# Autonomous-Car_Schematic-Extended.net
KiCad netlist of a schematic drawn in EAGLE
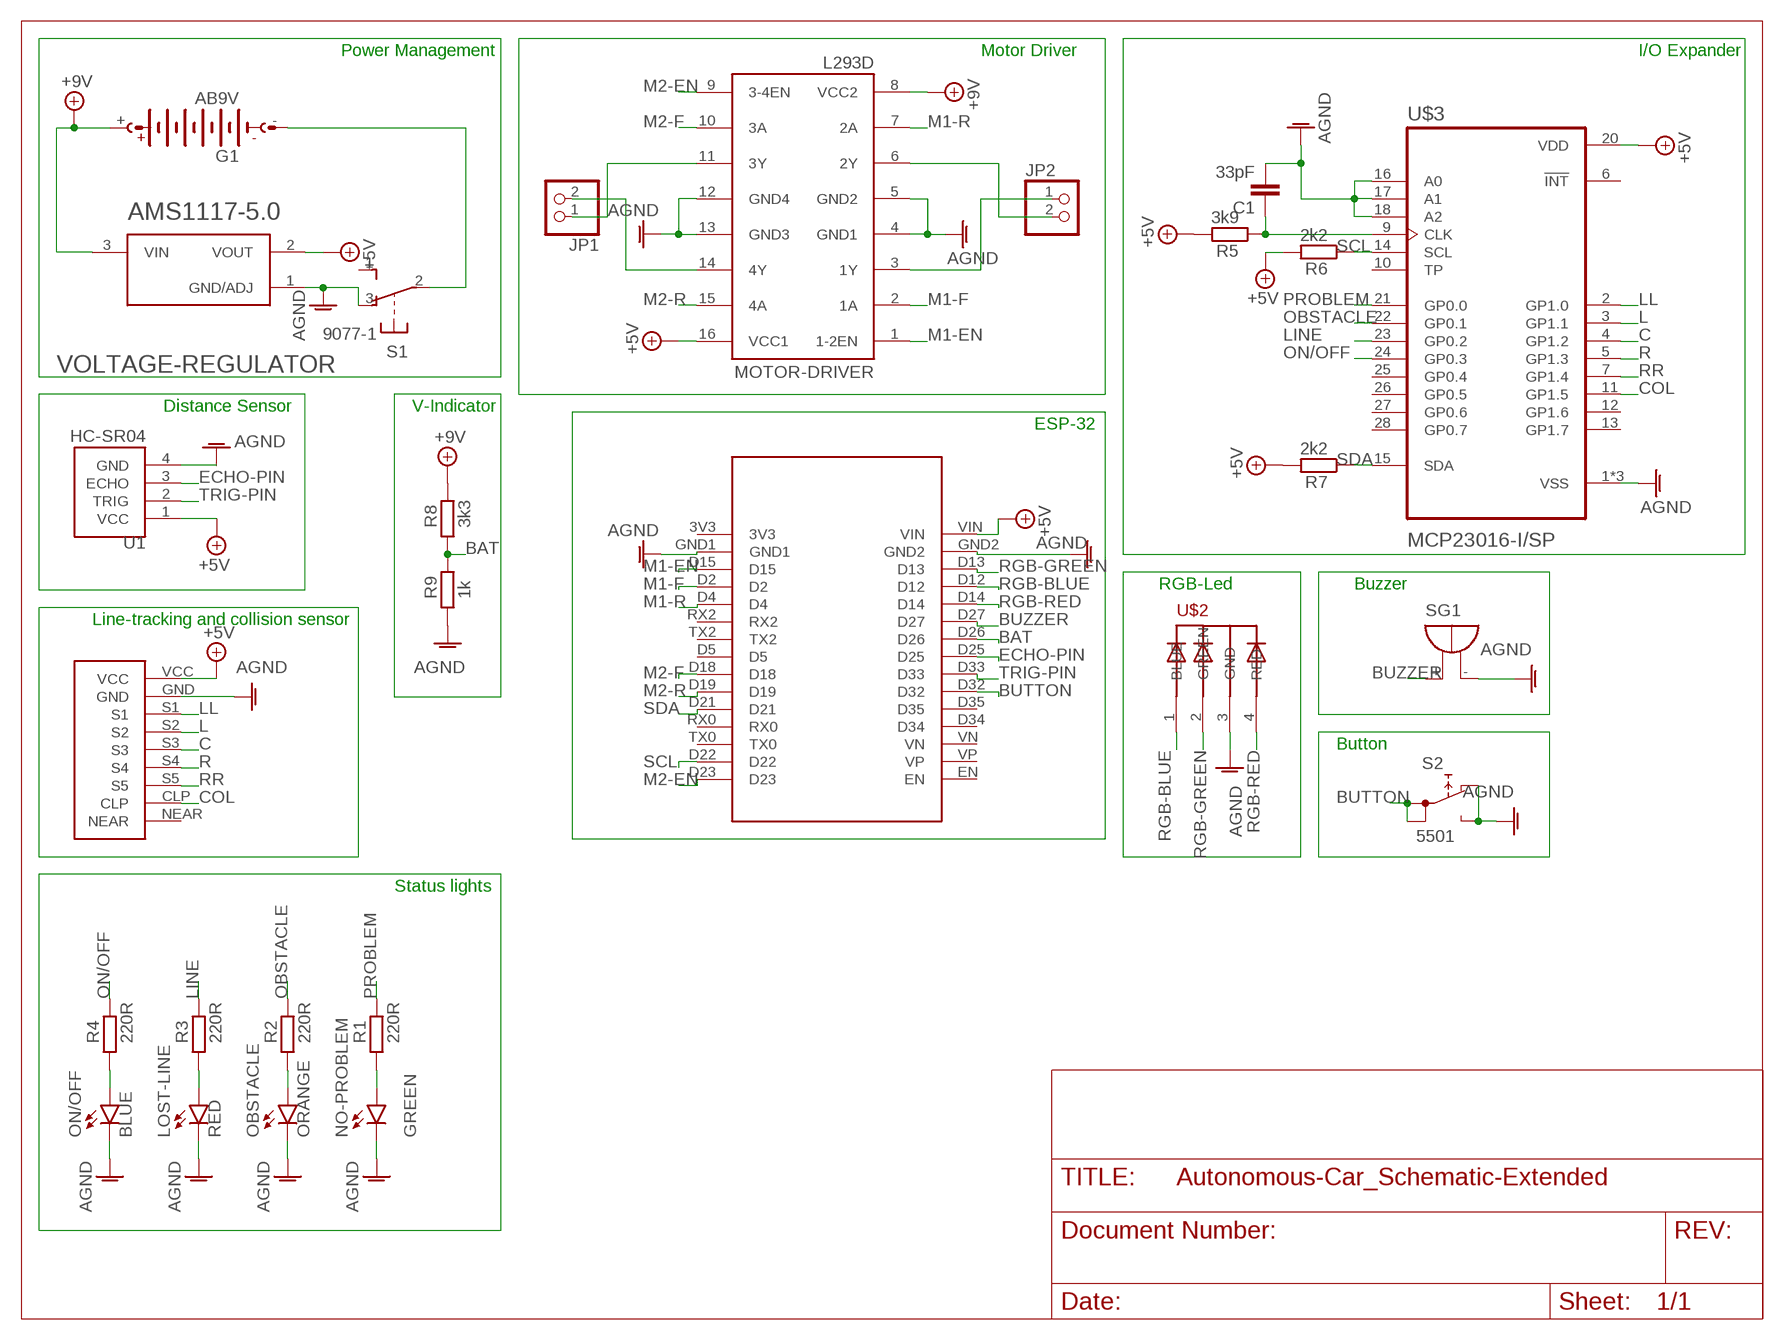
[diagram p0: schematic, sheet 1]

(export (version "E")
  (design (tool "Eeschema 10.0.6"))
  (components
    (comp (ref "C1")
      (value "33pF")
      (footprint "eagle-import:C025-024X044")
      (libsource (lib "eagle-import") (part "C-EU025-024X044"))
    )
    (comp (ref "G1")
      (value "AB9V")
      (footprint "eagle-import:AB9V")
      (libsource (lib "eagle-import") (part "AB9V"))
    )
    (comp (ref "JP1")
      (value "PINHD-1X2")
      (footprint "eagle-import:1X02")
      (libsource (lib "eagle-import") (part "PINHD-1X2"))
    )
    (comp (ref "JP2")
      (value "PINHD-1X2")
      (footprint "eagle-import:1X02")
      (libsource (lib "eagle-import") (part "PINHD-1X2"))
    )
    (comp (ref "LINETRACKER")
      (value "5XTCRT5000")
      (footprint "eagle-import:5XTCRT5000")
      (libsource (lib "eagle-import") (part "5XTCRT5000"))
    )
    (comp (ref "LOST-LINE")
      (value "RED")
      (footprint "eagle-import:LED5MM")
      (libsource (lib "eagle-import") (part "LED5MM"))
    )
    (comp (ref "MOTOR-DRIVER")
      (value "L293D")
      (footprint "eagle-import:DIL16")
      (libsource (lib "eagle-import") (part "L293D"))
    )
    (comp (ref "NO-PROBLEM")
      (value "GREEN")
      (footprint "eagle-import:LED5MM")
      (libsource (lib "eagle-import") (part "LED5MM"))
    )
    (comp (ref "OBSTACLE")
      (value "ORANGE")
      (footprint "eagle-import:LED5MM")
      (libsource (lib "eagle-import") (part "LED5MM"))
    )
    (comp (ref "ON/OFF")
      (value "BLUE")
      (footprint "eagle-import:LED5MM")
      (libsource (lib "eagle-import") (part "LED5MM"))
    )
    (comp (ref "R1")
      (value "220R")
      (footprint "eagle-import:0204_5")
      (libsource (lib "eagle-import") (part "R-EU_0204/5"))
    )
    (comp (ref "R2")
      (value "220R")
      (footprint "eagle-import:0204_5")
      (libsource (lib "eagle-import") (part "R-EU_0204/5"))
    )
    (comp (ref "R3")
      (value "220R")
      (footprint "eagle-import:0204_5")
      (libsource (lib "eagle-import") (part "R-EU_0204/5"))
    )
    (comp (ref "R4")
      (value "220R")
      (footprint "eagle-import:0204_5")
      (libsource (lib "eagle-import") (part "R-EU_0204/5"))
    )
    (comp (ref "R5")
      (value "3k9")
      (footprint "eagle-import:0204_5")
      (libsource (lib "eagle-import") (part "R-EU_0204/5"))
    )
    (comp (ref "R6")
      (value "2k2")
      (footprint "eagle-import:0204_5")
      (libsource (lib "eagle-import") (part "R-EU_0204/5"))
    )
    (comp (ref "R7")
      (value "2k2")
      (footprint "eagle-import:0204_5")
      (libsource (lib "eagle-import") (part "R-EU_0204/5"))
    )
    (comp (ref "R8")
      (value "3k3")
      (footprint "eagle-import:0204_5")
      (libsource (lib "eagle-import") (part "R-EU_0204/5"))
    )
    (comp (ref "R9")
      (value "1k")
      (footprint "eagle-import:0204_5")
      (libsource (lib "eagle-import") (part "R-EU_0204/5"))
    )
    (comp (ref "S1")
      (value "9077-1")
      (footprint "eagle-import:9077-1")
      (libsource (lib "eagle-import") (part "9077-1"))
    )
    (comp (ref "S2")
      (value "5501")
      (footprint "eagle-import:5501")
      (libsource (lib "eagle-import") (part "55?01"))
    )
    (comp (ref "SG1")
      (value "EB2209A")
      (footprint "eagle-import:EB2209A")
      (libsource (lib "eagle-import") (part "EB2209A"))
    )
    (comp (ref "U$1")
      (value "ESP32")
      (footprint "eagle-import:ESP32-FOOTPRINT")
      (libsource (lib "eagle-import") (part "ESP32"))
    )
    (comp (ref "U$2")
      (value "5MMRGBLED")
      (footprint "eagle-import:LED5MMRGB")
      (libsource (lib "eagle-import") (part "5MMRGBLED"))
    )
    (comp (ref "U$3")
      (value "MCP23016-I/SP")
      (footprint "eagle-import:DIP787W46P254L3467H508Q28")
      (fields (field (name "MF") "Microchip Technology"))
      (libsource (lib "eagle-import") (part "MCP23016-I/SP"))
    )
    (comp (ref "U1")
      (value "HC-SR04")
      (footprint "eagle-import:XCVR_HC-SR04")
      (fields (field (name "MF") "SparkFun Electronics"))
      (libsource (lib "eagle-import") (part "HC-SR04"))
    )
    (comp (ref "VOLTAGE-REGULATOR")
      (value "AMS1117-5.0")
      (footprint "eagle-import:SOT229P700X180-4N")
      (fields (field (name "MF") "Advanced Monolithic Systems"))
      (libsource (lib "eagle-import") (part "AMS1117-5.0"))
    )
  )
  (nets
    (net (code "1") (name "+5V") (class "Default")
      (node (ref "LINETRACKER") (pin "VCC") (pinfunction "VCC_VCC") (pintype "bidirectional"))
      (node (ref "MOTOR-DRIVER") (pin "16") (pinfunction "VCC1_16") (pintype "power_in"))
      (node (ref "R5") (pin "2") (pinfunction "2_2") (pintype "passive"))
      (node (ref "R6") (pin "2") (pinfunction "2_2") (pintype "passive"))
      (node (ref "R7") (pin "2") (pinfunction "2_2") (pintype "passive"))
      (node (ref "U$1") (pin "VIN") (pinfunction "VIN_VIN") (pintype "bidirectional"))
      (node (ref "U$3") (pin "20") (pinfunction "VDD_20") (pintype "power_in"))
      (node (ref "U1") (pin "1") (pinfunction "VCC_1") (pintype "power_in"))
      (node (ref "VOLTAGE-REGULATOR") (pin "2") (pinfunction "VOUT_2") (pintype "output"))
    )
    (net (code "2") (name "+9V") (class "Default")
      (node (ref "G1") (pin "+") (pinfunction "+_+") (pintype "passive"))
      (node (ref "MOTOR-DRIVER") (pin "8") (pinfunction "VCC2_8") (pintype "power_in"))
      (node (ref "R8") (pin "2") (pinfunction "2_2") (pintype "passive"))
      (node (ref "VOLTAGE-REGULATOR") (pin "3") (pinfunction "VIN_3") (pintype "input"))
    )
    (net (code "3") (name "/BAT") (class "Default")
      (node (ref "R8") (pin "1") (pinfunction "1_1") (pintype "passive"))
      (node (ref "R9") (pin "2") (pinfunction "2_2") (pintype "passive"))
      (node (ref "U$1") (pin "D26") (pinfunction "D26_D26") (pintype "bidirectional"))
    )
    (net (code "4") (name "/BUTTON") (class "Default")
      (node (ref "S2") (pin "1A") (pinfunction "1A_1A") (pintype "passive"))
      (node (ref "S2") (pin "1B") (pinfunction "1B_1B") (pintype "passive"))
      (node (ref "U$1") (pin "D32") (pinfunction "D32_D32") (pintype "bidirectional"))
    )
    (net (code "5") (name "/BUZZER") (class "Default")
      (node (ref "SG1") (pin "+") (pinfunction "+_+") (pintype "passive"))
      (node (ref "U$1") (pin "D27") (pinfunction "D27_D27") (pintype "bidirectional"))
    )
    (net (code "6") (name "/C") (class "Default")
      (node (ref "LINETRACKER") (pin "S3") (pinfunction "S3_S3") (pintype "bidirectional"))
      (node (ref "U$3") (pin "4") (pinfunction "GP1.2_4") (pintype "bidirectional"))
    )
    (net (code "7") (name "/COL") (class "Default")
      (node (ref "LINETRACKER") (pin "CLP") (pinfunction "CLP_CLP") (pintype "bidirectional"))
      (node (ref "U$3") (pin "11") (pinfunction "GP1.5_11") (pintype "bidirectional"))
    )
    (net (code "8") (name "/ECHO-PIN") (class "Default")
      (node (ref "U$1") (pin "D25") (pinfunction "D25_D25") (pintype "bidirectional"))
      (node (ref "U1") (pin "3") (pinfunction "ECHO_3") (pintype "bidirectional"))
    )
    (net (code "9") (name "/L") (class "Default")
      (node (ref "LINETRACKER") (pin "S2") (pinfunction "S2_S2") (pintype "bidirectional"))
      (node (ref "U$3") (pin "3") (pinfunction "GP1.1_3") (pintype "bidirectional"))
    )
    (net (code "10") (name "/LINE") (class "Default")
      (node (ref "R3") (pin "2") (pinfunction "2_2") (pintype "passive"))
      (node (ref "U$3") (pin "23") (pinfunction "GP0.2_23") (pintype "bidirectional"))
    )
    (net (code "11") (name "/LL") (class "Default")
      (node (ref "LINETRACKER") (pin "S1") (pinfunction "S1_S1") (pintype "bidirectional"))
      (node (ref "U$3") (pin "2") (pinfunction "GP1.0_2") (pintype "bidirectional"))
    )
    (net (code "12") (name "/M1-EN") (class "Default")
      (node (ref "MOTOR-DRIVER") (pin "1") (pinfunction "1-2EN_1") (pintype "input"))
      (node (ref "U$1") (pin "D15") (pinfunction "D15_D15") (pintype "bidirectional"))
    )
    (net (code "13") (name "/M1-F") (class "Default")
      (node (ref "MOTOR-DRIVER") (pin "2") (pinfunction "1A_2") (pintype "input"))
      (node (ref "U$1") (pin "D2") (pinfunction "D2_D2") (pintype "bidirectional"))
    )
    (net (code "14") (name "/M1-R") (class "Default")
      (node (ref "MOTOR-DRIVER") (pin "7") (pinfunction "2A_7") (pintype "input"))
      (node (ref "U$1") (pin "D4") (pinfunction "D4_D4") (pintype "bidirectional"))
    )
    (net (code "15") (name "/M2-EN") (class "Default")
      (node (ref "MOTOR-DRIVER") (pin "9") (pinfunction "3-4EN_9") (pintype "input"))
      (node (ref "U$1") (pin "D23") (pinfunction "D23_D23") (pintype "bidirectional"))
    )
    (net (code "16") (name "/M2-F") (class "Default")
      (node (ref "MOTOR-DRIVER") (pin "10") (pinfunction "3A_10") (pintype "input"))
      (node (ref "U$1") (pin "D18") (pinfunction "D18_D18") (pintype "bidirectional"))
    )
    (net (code "17") (name "/M2-R") (class "Default")
      (node (ref "MOTOR-DRIVER") (pin "15") (pinfunction "4A_15") (pintype "input"))
      (node (ref "U$1") (pin "D19") (pinfunction "D19_D19") (pintype "bidirectional"))
    )
    (net (code "18") (name "/OBSTACLE") (class "Default")
      (node (ref "R2") (pin "2") (pinfunction "2_2") (pintype "passive"))
      (node (ref "U$3") (pin "22") (pinfunction "GP0.1_22") (pintype "bidirectional"))
    )
    (net (code "19") (name "/ON{slash}OFF") (class "Default")
      (node (ref "R4") (pin "2") (pinfunction "2_2") (pintype "passive"))
      (node (ref "U$3") (pin "24") (pinfunction "GP0.3_24") (pintype "bidirectional"))
    )
    (net (code "20") (name "/PROBLEM") (class "Default")
      (node (ref "R1") (pin "2") (pinfunction "2_2") (pintype "passive"))
      (node (ref "U$3") (pin "21") (pinfunction "GP0.0_21") (pintype "bidirectional"))
    )
    (net (code "21") (name "/R") (class "Default")
      (node (ref "LINETRACKER") (pin "S4") (pinfunction "S4_S4") (pintype "bidirectional"))
      (node (ref "U$3") (pin "5") (pinfunction "GP1.3_5") (pintype "bidirectional"))
    )
    (net (code "22") (name "/RGB-BLUE") (class "Default")
      (node (ref "U$1") (pin "D12") (pinfunction "D12_D12") (pintype "bidirectional"))
      (node (ref "U$2") (pin "1") (pinfunction "BLUE_1") (pintype "bidirectional"))
    )
    (net (code "23") (name "/RGB-GREEN") (class "Default")
      (node (ref "U$1") (pin "D13") (pinfunction "D13_D13") (pintype "bidirectional"))
      (node (ref "U$2") (pin "2") (pinfunction "GREEN_2") (pintype "bidirectional"))
    )
    (net (code "24") (name "/RGB-RED") (class "Default")
      (node (ref "U$1") (pin "D14") (pinfunction "D14_D14") (pintype "bidirectional"))
      (node (ref "U$2") (pin "4") (pinfunction "RED_4") (pintype "bidirectional"))
    )
    (net (code "25") (name "/RR") (class "Default")
      (node (ref "LINETRACKER") (pin "S5") (pinfunction "S5_S5") (pintype "bidirectional"))
      (node (ref "U$3") (pin "7") (pinfunction "GP1.4_7") (pintype "bidirectional"))
    )
    (net (code "26") (name "/SCL") (class "Default")
      (node (ref "R6") (pin "1") (pinfunction "1_1") (pintype "passive"))
      (node (ref "U$1") (pin "D22") (pinfunction "D22_D22") (pintype "bidirectional"))
      (node (ref "U$3") (pin "14") (pinfunction "SCL_14") (pintype "input"))
    )
    (net (code "27") (name "/SDA") (class "Default")
      (node (ref "R7") (pin "1") (pinfunction "1_1") (pintype "passive"))
      (node (ref "U$1") (pin "D21") (pinfunction "D21_D21") (pintype "bidirectional"))
      (node (ref "U$3") (pin "15") (pinfunction "SDA_15") (pintype "bidirectional"))
    )
    (net (code "28") (name "/TRIG-PIN") (class "Default")
      (node (ref "U$1") (pin "D33") (pinfunction "D33_D33") (pintype "bidirectional"))
      (node (ref "U1") (pin "2") (pinfunction "TRIG_2") (pintype "bidirectional"))
    )
    (net (code "29") (name "AGND") (class "Default")
      (node (ref "C1") (pin "2") (pinfunction "2_2") (pintype "passive"))
      (node (ref "LINETRACKER") (pin "GND") (pinfunction "GND_GND") (pintype "bidirectional"))
      (node (ref "LOST-LINE") (pin "K") (pinfunction "C_K") (pintype "passive"))
      (node (ref "MOTOR-DRIVER") (pin "12") (pinfunction "GND4_12") (pintype "power_in"))
      (node (ref "MOTOR-DRIVER") (pin "13") (pinfunction "GND3_13") (pintype "power_in"))
      (node (ref "MOTOR-DRIVER") (pin "4") (pinfunction "GND1_4") (pintype "power_in"))
      (node (ref "MOTOR-DRIVER") (pin "5") (pinfunction "GND2_5") (pintype "power_in"))
      (node (ref "NO-PROBLEM") (pin "K") (pinfunction "C_K") (pintype "passive"))
      (node (ref "OBSTACLE") (pin "K") (pinfunction "C_K") (pintype "passive"))
      (node (ref "ON/OFF") (pin "K") (pinfunction "C_K") (pintype "passive"))
      (node (ref "R9") (pin "1") (pinfunction "1_1") (pintype "passive"))
      (node (ref "S1") (pin "3") (pinfunction "O_3") (pintype "passive"))
      (node (ref "S2") (pin "NC") (pinfunction "NC_NC") (pintype "passive"))
      (node (ref "S2") (pin "NO") (pinfunction "NO_NO") (pintype "passive"))
      (node (ref "SG1") (pin "-") (pinfunction "-_-") (pintype "passive"))
      (node (ref "U$1") (pin "GND1") (pinfunction "GND1_GND1") (pintype "bidirectional"))
      (node (ref "U$1") (pin "GND2") (pinfunction "GND2_GND2") (pintype "bidirectional"))
      (node (ref "U$2") (pin "3") (pinfunction "GND_3") (pintype "bidirectional"))
      (node (ref "U$3") (pin "1") (pinfunction "VSS_1") (pintype "power_in"))
      (node (ref "U$3") (pin "16") (pinfunction "A0_16") (pintype "input"))
      (node (ref "U$3") (pin "17") (pinfunction "A1_17") (pintype "input"))
      (node (ref "U$3") (pin "18") (pinfunction "A2_18") (pintype "input"))
      (node (ref "U$3") (pin "19") (pinfunction "VSS_19") (pintype "power_in"))
      (node (ref "U$3") (pin "8") (pinfunction "VSS_8") (pintype "power_in"))
      (node (ref "U1") (pin "4") (pinfunction "GND_4") (pintype "power_in"))
      (node (ref "VOLTAGE-REGULATOR") (pin "1") (pinfunction "GND/ADJ_1") (pintype "power_in"))
    )
    (net (code "30") (name "Net-(LOST-LINE-PadA)") (class "Default")
      (node (ref "LOST-LINE") (pin "A") (pinfunction "A_A") (pintype "passive"))
      (node (ref "R3") (pin "1") (pinfunction "1_1") (pintype "passive"))
    )
    (net (code "31") (name "Net-(MOTOR-DRIVER-1Y)") (class "Default")
      (node (ref "JP2") (pin "1") (pinfunction "1_1") (pintype "passive"))
      (node (ref "MOTOR-DRIVER") (pin "3") (pinfunction "1Y_3") (pintype "output"))
    )
    (net (code "32") (name "Net-(MOTOR-DRIVER-2Y)") (class "Default")
      (node (ref "JP2") (pin "2") (pinfunction "2_2") (pintype "passive"))
      (node (ref "MOTOR-DRIVER") (pin "6") (pinfunction "2Y_6") (pintype "output"))
    )
    (net (code "33") (name "Net-(MOTOR-DRIVER-3Y)") (class "Default")
      (node (ref "JP1") (pin "1") (pinfunction "1_1") (pintype "passive"))
      (node (ref "MOTOR-DRIVER") (pin "11") (pinfunction "3Y_11") (pintype "output"))
    )
    (net (code "34") (name "Net-(MOTOR-DRIVER-4Y)") (class "Default")
      (node (ref "JP1") (pin "2") (pinfunction "2_2") (pintype "passive"))
      (node (ref "MOTOR-DRIVER") (pin "14") (pinfunction "4Y_14") (pintype "output"))
    )
    (net (code "35") (name "Net-(NO-PROBLEM-PadA)") (class "Default")
      (node (ref "NO-PROBLEM") (pin "A") (pinfunction "A_A") (pintype "passive"))
      (node (ref "R1") (pin "1") (pinfunction "1_1") (pintype "passive"))
    )
    (net (code "36") (name "Net-(OBSTACLE-PadA)") (class "Default")
      (node (ref "OBSTACLE") (pin "A") (pinfunction "A_A") (pintype "passive"))
      (node (ref "R2") (pin "1") (pinfunction "1_1") (pintype "passive"))
    )
    (net (code "37") (name "Net-(ON/OFF-PadA)") (class "Default")
      (node (ref "ON/OFF") (pin "A") (pinfunction "A_A") (pintype "passive"))
      (node (ref "R4") (pin "1") (pinfunction "1_1") (pintype "passive"))
    )
    (net (code "38") (name "Net-(S1-P)") (class "Default")
      (node (ref "G1") (pin "-") (pinfunction "-_-") (pintype "passive"))
      (node (ref "S1") (pin "2") (pinfunction "P_2") (pintype "passive"))
    )
    (net (code "39") (name "Net-(U$3-CLK)") (class "Default")
      (node (ref "C1") (pin "1") (pinfunction "1_1") (pintype "passive"))
      (node (ref "R5") (pin "1") (pinfunction "1_1") (pintype "passive"))
      (node (ref "U$3") (pin "9") (pinfunction "CLK_9") (pintype "input"))
    )
    (net (code "40") (name "unconnected-(LINETRACKER-PadNEAR)") (class "Default")
      (node (ref "LINETRACKER") (pin "NEAR") (pinfunction "NEAR_NEAR") (pintype "bidirectional"))
    )
    (net (code "41") (name "unconnected-(S1-S-Pad1)") (class "Default")
      (node (ref "S1") (pin "1") (pinfunction "S_1") (pintype "passive"))
    )
    (net (code "42") (name "unconnected-(U$1-Pad3V3)") (class "Default")
      (node (ref "U$1") (pin "3V3") (pinfunction "3V3_3V3") (pintype "bidirectional"))
    )
    (net (code "43") (name "unconnected-(U$1-PadD5)") (class "Default")
      (node (ref "U$1") (pin "D5") (pinfunction "D5_D5") (pintype "bidirectional"))
    )
    (net (code "44") (name "unconnected-(U$1-PadD34)") (class "Default")
      (node (ref "U$1") (pin "D34") (pinfunction "D34_D34") (pintype "bidirectional"))
    )
    (net (code "45") (name "unconnected-(U$1-PadD35)") (class "Default")
      (node (ref "U$1") (pin "D35") (pinfunction "D35_D35") (pintype "bidirectional"))
    )
    (net (code "46") (name "unconnected-(U$1-PadEN)") (class "Default")
      (node (ref "U$1") (pin "EN") (pinfunction "EN_EN") (pintype "bidirectional"))
    )
    (net (code "47") (name "unconnected-(U$1-PadRX0)") (class "Default")
      (node (ref "U$1") (pin "RX0") (pinfunction "RX0_RX0") (pintype "bidirectional"))
    )
    (net (code "48") (name "unconnected-(U$1-PadRX2)") (class "Default")
      (node (ref "U$1") (pin "RX2") (pinfunction "RX2_RX2") (pintype "bidirectional"))
    )
    (net (code "49") (name "unconnected-(U$1-PadTX0)") (class "Default")
      (node (ref "U$1") (pin "TX0") (pinfunction "TX0_TX0") (pintype "bidirectional"))
    )
    (net (code "50") (name "unconnected-(U$1-PadTX2)") (class "Default")
      (node (ref "U$1") (pin "TX2") (pinfunction "TX2_TX2") (pintype "bidirectional"))
    )
    (net (code "51") (name "unconnected-(U$1-PadVN)") (class "Default")
      (node (ref "U$1") (pin "VN") (pinfunction "VN_VN") (pintype "bidirectional"))
    )
    (net (code "52") (name "unconnected-(U$1-PadVP)") (class "Default")
      (node (ref "U$1") (pin "VP") (pinfunction "VP_VP") (pintype "bidirectional"))
    )
    (net (code "53") (name "unconnected-(U$3-GP0.4-Pad25)") (class "Default")
      (node (ref "U$3") (pin "25") (pinfunction "GP0.4_25") (pintype "bidirectional"))
    )
    (net (code "54") (name "unconnected-(U$3-GP0.5-Pad26)") (class "Default")
      (node (ref "U$3") (pin "26") (pinfunction "GP0.5_26") (pintype "bidirectional"))
    )
    (net (code "55") (name "unconnected-(U$3-GP0.6-Pad27)") (class "Default")
      (node (ref "U$3") (pin "27") (pinfunction "GP0.6_27") (pintype "bidirectional"))
    )
    (net (code "56") (name "unconnected-(U$3-GP0.7-Pad28)") (class "Default")
      (node (ref "U$3") (pin "28") (pinfunction "GP0.7_28") (pintype "bidirectional"))
    )
    (net (code "57") (name "unconnected-(U$3-GP1.6-Pad12)") (class "Default")
      (node (ref "U$3") (pin "12") (pinfunction "GP1.6_12") (pintype "bidirectional"))
    )
    (net (code "58") (name "unconnected-(U$3-GP1.7-Pad13)") (class "Default")
      (node (ref "U$3") (pin "13") (pinfunction "GP1.7_13") (pintype "bidirectional"))
    )
    (net (code "59") (name "unconnected-(U$3-TP-Pad10)") (class "Default")
      (node (ref "U$3") (pin "10") (pinfunction "TP_10") (pintype "input"))
    )
    (net (code "60") (name "unconnected-(U$3-~{INT}-Pad6)") (class "Default")
      (node (ref "U$3") (pin "6") (pinfunction "~{INT}_6") (pintype "output"))
    )
  )
)
